# AdafruitHuzzah32Base.net
KiCad netlist of a schematic drawn in EAGLE
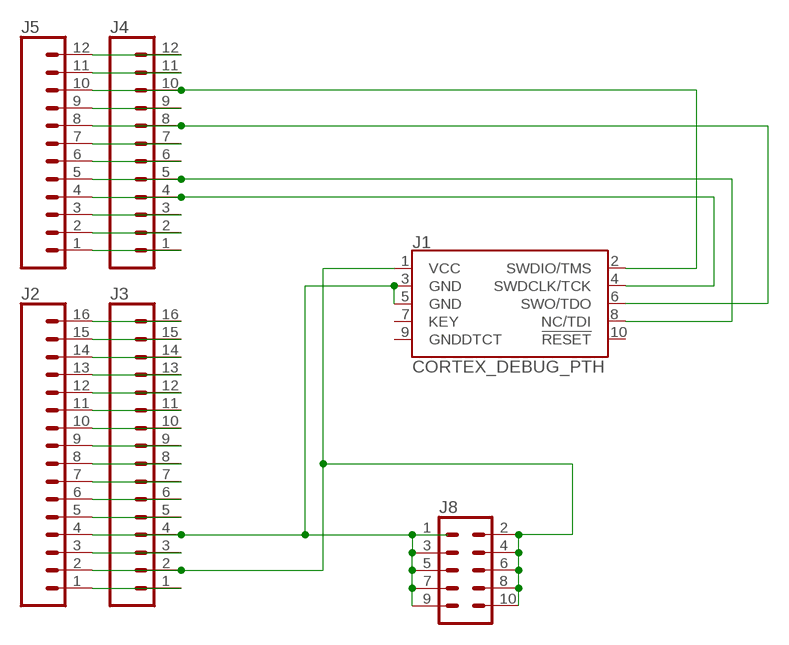
[diagram p0: schematic, sheet 1]

(export (version "E")
  (design (tool "Eeschema 10.0.6"))
  (components
    (comp (ref "J1")
      (value "CORTEX_DEBUG_PTH")
      (footprint "eagle-import:2X5-PTH-1.27MM")
      (libsource (lib "eagle-import") (part "CORTEX_DEBUG_PTH"))
    )
    (comp (ref "J2")
      (value "CONN_16")
      (footprint "eagle-import:1X16")
      (libsource (lib "eagle-import") (part "CONN_16"))
    )
    (comp (ref "J3")
      (value "CONN_16")
      (footprint "eagle-import:1X16")
      (libsource (lib "eagle-import") (part "CONN_16"))
    )
    (comp (ref "J4")
      (value "CONN_12")
      (footprint "eagle-import:1X12")
      (libsource (lib "eagle-import") (part "CONN_12"))
    )
    (comp (ref "J5")
      (value "CONN_12")
      (footprint "eagle-import:1X12")
      (libsource (lib "eagle-import") (part "CONN_12"))
    )
    (comp (ref "J8")
      (value "CONN_05X2PTH")
      (footprint "eagle-import:2X5")
      (libsource (lib "eagle-import") (part "CONN_05X2PTH"))
    )
  )
  (nets
    (net (code "1") (name "Net-(J1-GND-Pad3)") (class "Default")
      (node (ref "J1") (pin "3") (pinfunction "GND_3") (pintype "bidirectional"))
      (node (ref "J1") (pin "5") (pinfunction "GND_5") (pintype "bidirectional"))
      (node (ref "J2") (pin "4") (pinfunction "4_4") (pintype "passive"))
      (node (ref "J3") (pin "4") (pinfunction "4_4") (pintype "passive"))
      (node (ref "J8") (pin "1") (pinfunction "1_1") (pintype "passive"))
      (node (ref "J8") (pin "3") (pinfunction "3_3") (pintype "passive"))
      (node (ref "J8") (pin "5") (pinfunction "5_5") (pintype "passive"))
      (node (ref "J8") (pin "7") (pinfunction "7_7") (pintype "passive"))
      (node (ref "J8") (pin "9") (pinfunction "9_9") (pintype "passive"))
    )
    (net (code "2") (name "Net-(J1-NC{slash}TDI)") (class "Default")
      (node (ref "J1") (pin "8") (pinfunction "NC/TDI_8") (pintype "bidirectional"))
      (node (ref "J4") (pin "5") (pinfunction "5_5") (pintype "passive"))
      (node (ref "J5") (pin "5") (pinfunction "5_5") (pintype "passive"))
    )
    (net (code "3") (name "Net-(J1-SWDCLK{slash}TCK)") (class "Default")
      (node (ref "J1") (pin "4") (pinfunction "SWDCLK/TCK_4") (pintype "bidirectional"))
      (node (ref "J4") (pin "4") (pinfunction "4_4") (pintype "passive"))
      (node (ref "J5") (pin "4") (pinfunction "4_4") (pintype "passive"))
    )
    (net (code "4") (name "Net-(J1-SWDIO{slash}TMS)") (class "Default")
      (node (ref "J1") (pin "2") (pinfunction "SWDIO/TMS_2") (pintype "bidirectional"))
      (node (ref "J4") (pin "10") (pinfunction "10_10") (pintype "passive"))
      (node (ref "J5") (pin "10") (pinfunction "10_10") (pintype "passive"))
    )
    (net (code "5") (name "Net-(J1-SWO{slash}TDO)") (class "Default")
      (node (ref "J1") (pin "6") (pinfunction "SWO/TDO_6") (pintype "bidirectional"))
      (node (ref "J4") (pin "8") (pinfunction "8_8") (pintype "passive"))
      (node (ref "J5") (pin "8") (pinfunction "8_8") (pintype "passive"))
    )
    (net (code "6") (name "Net-(J1-VCC)") (class "Default")
      (node (ref "J1") (pin "1") (pinfunction "VCC_1") (pintype "bidirectional"))
      (node (ref "J2") (pin "2") (pinfunction "2_2") (pintype "passive"))
      (node (ref "J3") (pin "2") (pinfunction "2_2") (pintype "passive"))
      (node (ref "J8") (pin "10") (pinfunction "10_10") (pintype "passive"))
      (node (ref "J8") (pin "2") (pinfunction "2_2") (pintype "passive"))
      (node (ref "J8") (pin "4") (pinfunction "4_4") (pintype "passive"))
      (node (ref "J8") (pin "6") (pinfunction "6_6") (pintype "passive"))
      (node (ref "J8") (pin "8") (pinfunction "8_8") (pintype "passive"))
    )
    (net (code "7") (name "Net-(J2-Pad1)") (class "Default")
      (node (ref "J2") (pin "1") (pinfunction "1_1") (pintype "passive"))
      (node (ref "J3") (pin "1") (pinfunction "1_1") (pintype "passive"))
    )
    (net (code "8") (name "Net-(J2-Pad3)") (class "Default")
      (node (ref "J2") (pin "3") (pinfunction "3_3") (pintype "passive"))
      (node (ref "J3") (pin "3") (pinfunction "3_3") (pintype "passive"))
    )
    (net (code "9") (name "Net-(J2-Pad5)") (class "Default")
      (node (ref "J2") (pin "5") (pinfunction "5_5") (pintype "passive"))
      (node (ref "J3") (pin "5") (pinfunction "5_5") (pintype "passive"))
    )
    (net (code "10") (name "Net-(J2-Pad6)") (class "Default")
      (node (ref "J2") (pin "6") (pinfunction "6_6") (pintype "passive"))
      (node (ref "J3") (pin "6") (pinfunction "6_6") (pintype "passive"))
    )
    (net (code "11") (name "Net-(J2-Pad7)") (class "Default")
      (node (ref "J2") (pin "7") (pinfunction "7_7") (pintype "passive"))
      (node (ref "J3") (pin "7") (pinfunction "7_7") (pintype "passive"))
    )
    (net (code "12") (name "Net-(J2-Pad8)") (class "Default")
      (node (ref "J2") (pin "8") (pinfunction "8_8") (pintype "passive"))
      (node (ref "J3") (pin "8") (pinfunction "8_8") (pintype "passive"))
    )
    (net (code "13") (name "Net-(J2-Pad9)") (class "Default")
      (node (ref "J2") (pin "9") (pinfunction "9_9") (pintype "passive"))
      (node (ref "J3") (pin "9") (pinfunction "9_9") (pintype "passive"))
    )
    (net (code "14") (name "Net-(J2-Pad10)") (class "Default")
      (node (ref "J2") (pin "10") (pinfunction "10_10") (pintype "passive"))
      (node (ref "J3") (pin "10") (pinfunction "10_10") (pintype "passive"))
    )
    (net (code "15") (name "Net-(J2-Pad11)") (class "Default")
      (node (ref "J2") (pin "11") (pinfunction "11_11") (pintype "passive"))
      (node (ref "J3") (pin "11") (pinfunction "11_11") (pintype "passive"))
    )
    (net (code "16") (name "Net-(J2-Pad12)") (class "Default")
      (node (ref "J2") (pin "12") (pinfunction "12_12") (pintype "passive"))
      (node (ref "J3") (pin "12") (pinfunction "12_12") (pintype "passive"))
    )
    (net (code "17") (name "Net-(J2-Pad13)") (class "Default")
      (node (ref "J2") (pin "13") (pinfunction "13_13") (pintype "passive"))
      (node (ref "J3") (pin "13") (pinfunction "13_13") (pintype "passive"))
    )
    (net (code "18") (name "Net-(J2-Pad14)") (class "Default")
      (node (ref "J2") (pin "14") (pinfunction "14_14") (pintype "passive"))
      (node (ref "J3") (pin "14") (pinfunction "14_14") (pintype "passive"))
    )
    (net (code "19") (name "Net-(J2-Pad15)") (class "Default")
      (node (ref "J2") (pin "15") (pinfunction "15_15") (pintype "passive"))
      (node (ref "J3") (pin "15") (pinfunction "15_15") (pintype "passive"))
    )
    (net (code "20") (name "Net-(J2-Pad16)") (class "Default")
      (node (ref "J2") (pin "16") (pinfunction "16_16") (pintype "passive"))
      (node (ref "J3") (pin "16") (pinfunction "16_16") (pintype "passive"))
    )
    (net (code "21") (name "Net-(J4-Pad1)") (class "Default")
      (node (ref "J4") (pin "1") (pinfunction "1_1") (pintype "passive"))
      (node (ref "J5") (pin "1") (pinfunction "1_1") (pintype "passive"))
    )
    (net (code "22") (name "Net-(J4-Pad2)") (class "Default")
      (node (ref "J4") (pin "2") (pinfunction "2_2") (pintype "passive"))
      (node (ref "J5") (pin "2") (pinfunction "2_2") (pintype "passive"))
    )
    (net (code "23") (name "Net-(J4-Pad3)") (class "Default")
      (node (ref "J4") (pin "3") (pinfunction "3_3") (pintype "passive"))
      (node (ref "J5") (pin "3") (pinfunction "3_3") (pintype "passive"))
    )
    (net (code "24") (name "Net-(J4-Pad6)") (class "Default")
      (node (ref "J4") (pin "6") (pinfunction "6_6") (pintype "passive"))
      (node (ref "J5") (pin "6") (pinfunction "6_6") (pintype "passive"))
    )
    (net (code "25") (name "Net-(J4-Pad7)") (class "Default")
      (node (ref "J4") (pin "7") (pinfunction "7_7") (pintype "passive"))
      (node (ref "J5") (pin "7") (pinfunction "7_7") (pintype "passive"))
    )
    (net (code "26") (name "Net-(J4-Pad9)") (class "Default")
      (node (ref "J4") (pin "9") (pinfunction "9_9") (pintype "passive"))
      (node (ref "J5") (pin "9") (pinfunction "9_9") (pintype "passive"))
    )
    (net (code "27") (name "Net-(J4-Pad11)") (class "Default")
      (node (ref "J4") (pin "11") (pinfunction "11_11") (pintype "passive"))
      (node (ref "J5") (pin "11") (pinfunction "11_11") (pintype "passive"))
    )
    (net (code "28") (name "Net-(J4-Pad12)") (class "Default")
      (node (ref "J4") (pin "12") (pinfunction "12_12") (pintype "passive"))
      (node (ref "J5") (pin "12") (pinfunction "12_12") (pintype "passive"))
    )
    (net (code "29") (name "unconnected-(J1-GNDDTCT-Pad9)") (class "Default")
      (node (ref "J1") (pin "9") (pinfunction "GNDDTCT_9") (pintype "bidirectional"))
    )
    (net (code "30") (name "unconnected-(J1-KEY-Pad7)") (class "Default")
      (node (ref "J1") (pin "7") (pinfunction "KEY_7") (pintype "bidirectional"))
    )
    (net (code "31") (name "unconnected-(J1-~{RESET}-Pad10)") (class "Default")
      (node (ref "J1") (pin "10") (pinfunction "~{RESET}_10") (pintype "bidirectional"))
    )
  )
)
